# H4_PadController_Rev_1.net
KiCad netlist of a schematic drawn in EAGLE
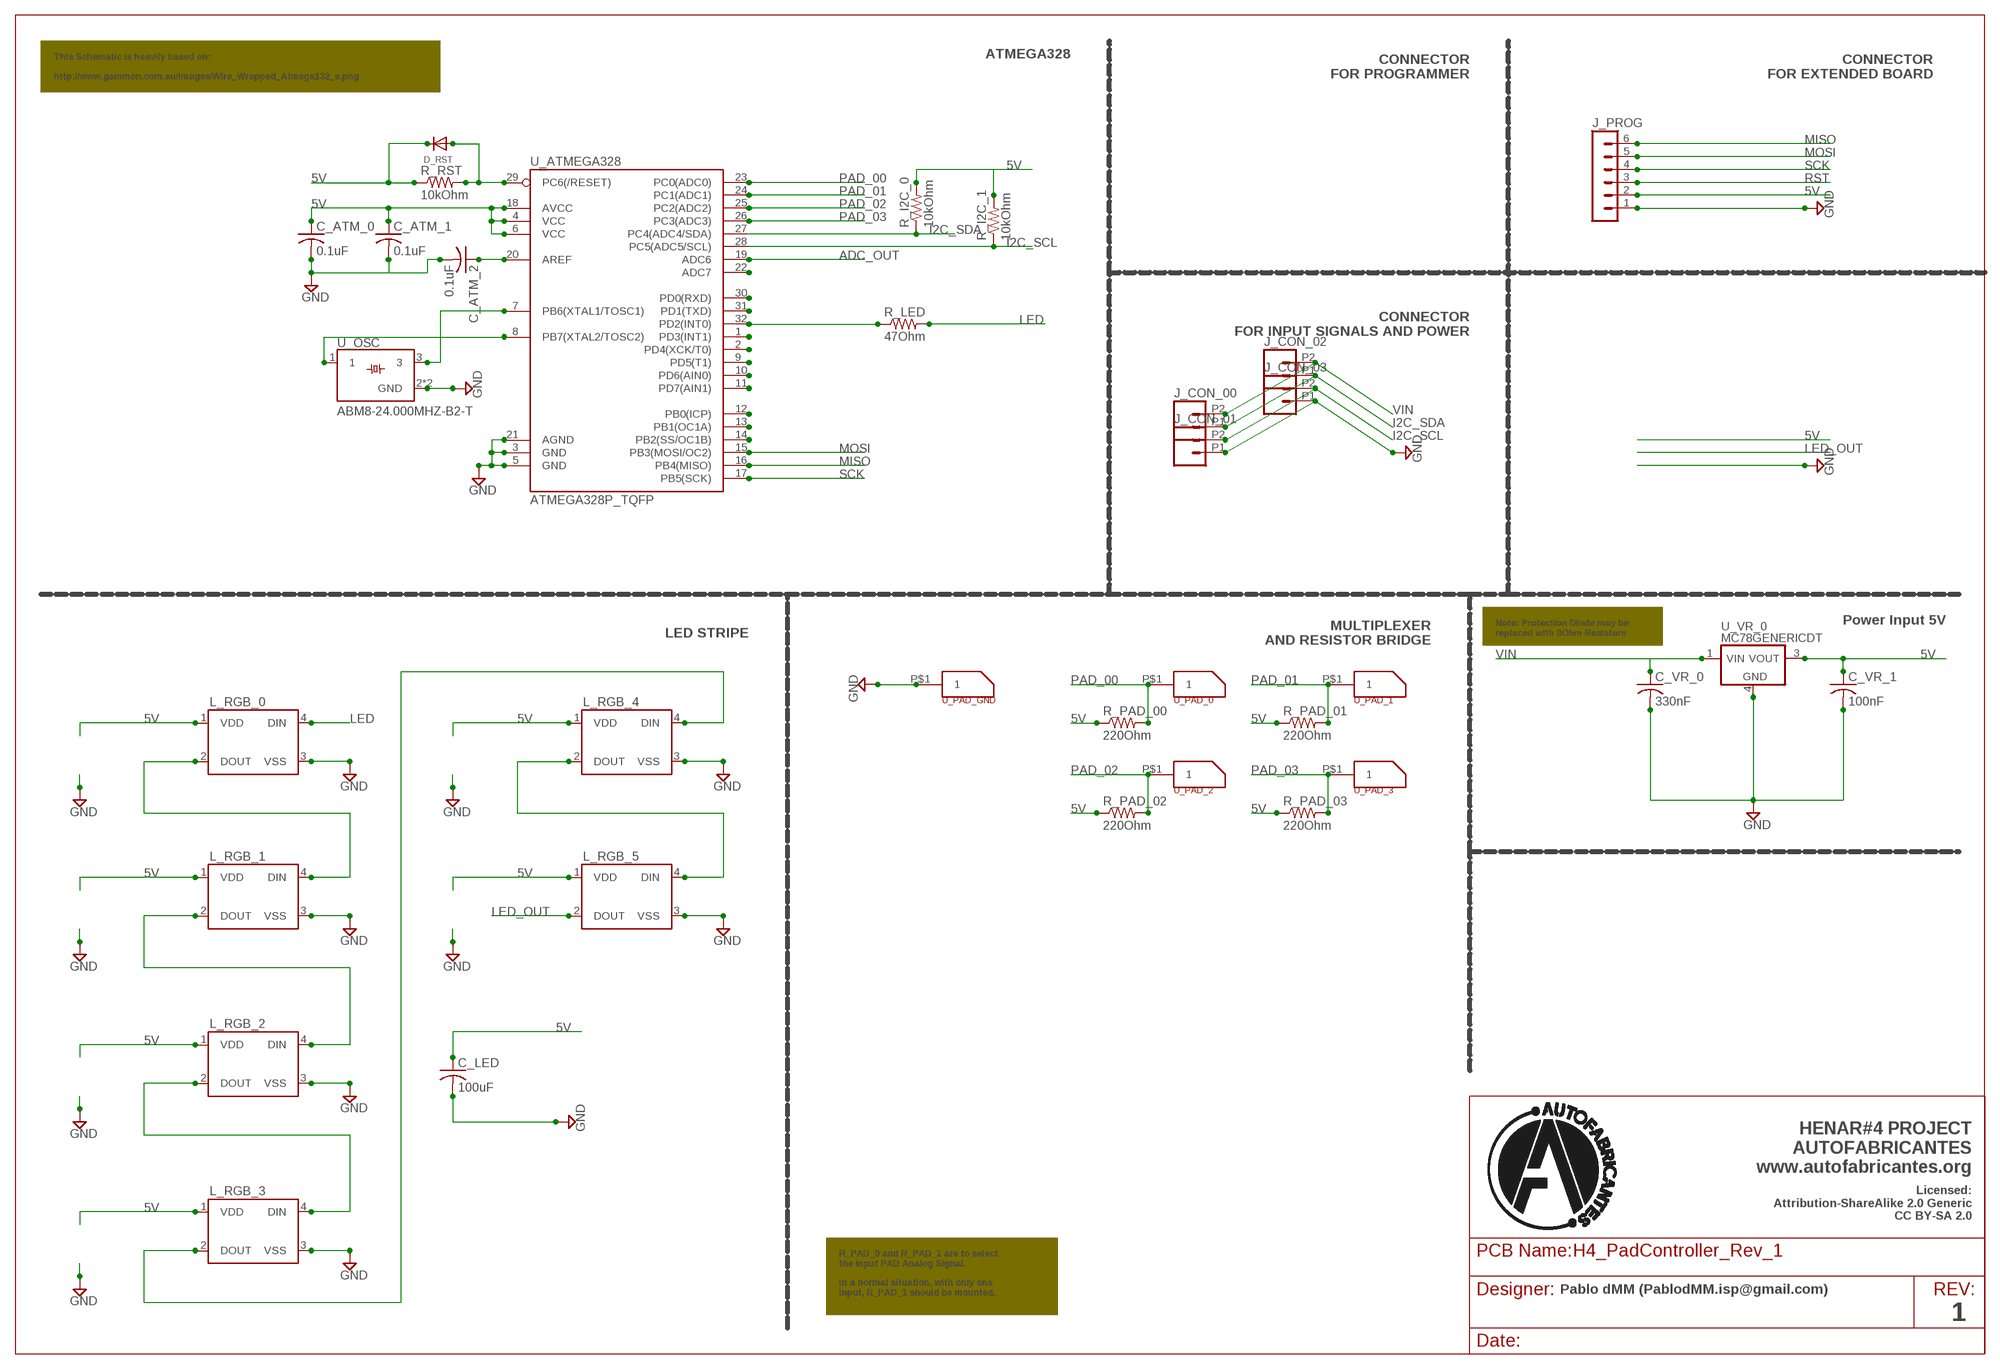
[diagram p0: schematic, sheet 1]

(export (version "E")
  (design (tool "Eeschema 10.0.6"))
  (components
    (comp (ref "C_ATM_0")
      (value "0.1uF")
      (footprint "eagle-import:C0805")
      (libsource (lib "eagle-import") (part "C-USC0805"))
    )
    (comp (ref "C_ATM_1")
      (value "0.1uF")
      (footprint "eagle-import:C0805")
      (libsource (lib "eagle-import") (part "C-USC0805"))
    )
    (comp (ref "C_ATM_2")
      (value "0.1uF")
      (footprint "eagle-import:C0805")
      (libsource (lib "eagle-import") (part "C-USC0805"))
    )
    (comp (ref "C_LED")
      (value "100uF")
      (footprint "eagle-import:C1210")
      (libsource (lib "eagle-import") (part "C-USC1210"))
    )
    (comp (ref "C_VR_0")
      (value "330nF")
      (footprint "eagle-import:C0805")
      (libsource (lib "eagle-import") (part "C-USC0805"))
    )
    (comp (ref "C_VR_1")
      (value "100nF")
      (footprint "eagle-import:C0805")
      (libsource (lib "eagle-import") (part "C-USC0805"))
    )
    (comp (ref "D_RST")
      (value "DIODESOD-123")
      (footprint "eagle-import:SOD-123")
      (libsource (lib "eagle-import") (part "DIODESOD-123"))
    )
    (comp (ref "J_CON_00")
      (value "M022.54MM_SCREWTERM")
      (footprint "eagle-import:1X02_2.54_SCREWTERM")
      (libsource (lib "eagle-import") (part "M022.54MM_SCREWTERM"))
    )
    (comp (ref "J_CON_01")
      (value "M022.54MM_SCREWTERM")
      (footprint "eagle-import:1X02_2.54_SCREWTERM")
      (libsource (lib "eagle-import") (part "M022.54MM_SCREWTERM"))
    )
    (comp (ref "J_CON_02")
      (value "M022.54MM_SCREWTERM")
      (footprint "eagle-import:1X02_2.54_SCREWTERM")
      (libsource (lib "eagle-import") (part "M022.54MM_SCREWTERM"))
    )
    (comp (ref "J_CON_03")
      (value "M022.54MM_SCREWTERM")
      (footprint "eagle-import:1X02_2.54_SCREWTERM")
      (libsource (lib "eagle-import") (part "M022.54MM_SCREWTERM"))
    )
    (comp (ref "J_PROG")
      (value "MA06-1")
      (footprint "eagle-import:MA06-1")
      (libsource (lib "eagle-import") (part "MA06-1"))
    )
    (comp (ref "L_RGB_0")
      (value "WS2812B")
      (footprint "eagle-import:WS2812B")
      (libsource (lib "eagle-import") (part "WS2812B"))
    )
    (comp (ref "L_RGB_1")
      (value "WS2812B")
      (footprint "eagle-import:WS2812B")
      (libsource (lib "eagle-import") (part "WS2812B"))
    )
    (comp (ref "L_RGB_2")
      (value "WS2812B")
      (footprint "eagle-import:WS2812B")
      (libsource (lib "eagle-import") (part "WS2812B"))
    )
    (comp (ref "L_RGB_3")
      (value "WS2812B")
      (footprint "eagle-import:WS2812B")
      (libsource (lib "eagle-import") (part "WS2812B"))
    )
    (comp (ref "L_RGB_4")
      (value "WS2812B")
      (footprint "eagle-import:WS2812B")
      (libsource (lib "eagle-import") (part "WS2812B"))
    )
    (comp (ref "L_RGB_5")
      (value "WS2812B")
      (footprint "eagle-import:WS2812B")
      (libsource (lib "eagle-import") (part "WS2812B"))
    )
    (comp (ref "R_I2C_0")
      (value "10kOhm")
      (footprint "eagle-import:M0805")
      (libsource (lib "eagle-import") (part "R-US_M0805"))
    )
    (comp (ref "R_I2C_1")
      (value "10kOhm")
      (footprint "eagle-import:M0805")
      (libsource (lib "eagle-import") (part "R-US_M0805"))
    )
    (comp (ref "R_LED")
      (value "47Ohm")
      (footprint "eagle-import:M0805")
      (libsource (lib "eagle-import") (part "R-US_M0805"))
    )
    (comp (ref "R_PAD_00")
      (value "220Ohm")
      (footprint "eagle-import:M0805")
      (libsource (lib "eagle-import") (part "R-US_M0805"))
    )
    (comp (ref "R_PAD_01")
      (value "220Ohm")
      (footprint "eagle-import:M0805")
      (libsource (lib "eagle-import") (part "R-US_M0805"))
    )
    (comp (ref "R_PAD_02")
      (value "220Ohm")
      (footprint "eagle-import:M0805")
      (libsource (lib "eagle-import") (part "R-US_M0805"))
    )
    (comp (ref "R_PAD_03")
      (value "220Ohm")
      (footprint "eagle-import:M0805")
      (libsource (lib "eagle-import") (part "R-US_M0805"))
    )
    (comp (ref "R_RST")
      (value "10kOhm")
      (footprint "eagle-import:M0805")
      (libsource (lib "eagle-import") (part "R-US_M0805"))
    )
    (comp (ref "U_ATMEGA328")
      (value "ATMEGA328P_TQFP")
      (footprint "eagle-import:TQFP32-08")
      (libsource (lib "eagle-import") (part "ATMEGA328P_TQFP"))
    )
    (comp (ref "U_OSC")
      (value "ABM8-24.000MHZ-B2-T")
      (footprint "eagle-import:OSCSC320X250X100N")
      (fields (field (name "MF") "Abracon"))
      (libsource (lib "eagle-import") (part "ABM8-24.000MHZ-B2-T"))
    )
    (comp (ref "U_PAD_0")
      (value "PAD_CONNECTOR_MULTI")
      (footprint "eagle-import:PAD_CONNECTOR_MULTI")
      (libsource (lib "eagle-import") (part "PAD_CONNECTOR_MULTI"))
    )
    (comp (ref "U_PAD_1")
      (value "PAD_CONNECTOR_MULTI")
      (footprint "eagle-import:PAD_CONNECTOR_MULTI")
      (libsource (lib "eagle-import") (part "PAD_CONNECTOR_MULTI"))
    )
    (comp (ref "U_PAD_2")
      (value "PAD_CONNECTOR_MULTI")
      (footprint "eagle-import:PAD_CONNECTOR_MULTI")
      (libsource (lib "eagle-import") (part "PAD_CONNECTOR_MULTI"))
    )
    (comp (ref "U_PAD_3")
      (value "PAD_CONNECTOR_MULTI")
      (footprint "eagle-import:PAD_CONNECTOR_MULTI")
      (libsource (lib "eagle-import") (part "PAD_CONNECTOR_MULTI"))
    )
    (comp (ref "U_PAD_GND")
      (value "PAD_CONNECTOR_MULTI")
      (footprint "eagle-import:PAD_CONNECTOR_MULTI")
      (libsource (lib "eagle-import") (part "PAD_CONNECTOR_MULTI"))
    )
    (comp (ref "U_VR_0")
      (value "MC78GENERICDT")
      (footprint "eagle-import:DPAK-3")
      (libsource (lib "eagle-import") (part "MC78DTGENERIC"))
    )
  )
  (nets
    (net (code "1") (name "/5V") (class "Default")
      (node (ref "C_ATM_0") (pin "1") (pinfunction "1_1") (pintype "passive"))
      (node (ref "C_ATM_1") (pin "1") (pinfunction "1_1") (pintype "passive"))
      (node (ref "C_LED") (pin "1") (pinfunction "1_1") (pintype "passive"))
      (node (ref "C_VR_1") (pin "1") (pinfunction "1_1") (pintype "passive"))
      (node (ref "D_RST") (pin "C") (pinfunction "C_C") (pintype "passive"))
      (node (ref "J_PROG") (pin "2") (pinfunction "2_2") (pintype "passive"))
      (node (ref "L_RGB_0") (pin "1") (pinfunction "VDD_1") (pintype "power_in"))
      (node (ref "L_RGB_1") (pin "1") (pinfunction "VDD_1") (pintype "power_in"))
      (node (ref "L_RGB_2") (pin "1") (pinfunction "VDD_1") (pintype "power_in"))
      (node (ref "L_RGB_3") (pin "1") (pinfunction "VDD_1") (pintype "power_in"))
      (node (ref "L_RGB_4") (pin "1") (pinfunction "VDD_1") (pintype "power_in"))
      (node (ref "L_RGB_5") (pin "1") (pinfunction "VDD_1") (pintype "power_in"))
      (node (ref "R_I2C_0") (pin "2") (pinfunction "2_2") (pintype "passive"))
      (node (ref "R_I2C_1") (pin "2") (pinfunction "2_2") (pintype "passive"))
      (node (ref "R_PAD_00") (pin "1") (pinfunction "1_1") (pintype "passive"))
      (node (ref "R_PAD_01") (pin "1") (pinfunction "1_1") (pintype "passive"))
      (node (ref "R_PAD_02") (pin "1") (pinfunction "1_1") (pintype "passive"))
      (node (ref "R_PAD_03") (pin "1") (pinfunction "1_1") (pintype "passive"))
      (node (ref "R_RST") (pin "1") (pinfunction "1_1") (pintype "passive"))
      (node (ref "U_ATMEGA328") (pin "18") (pinfunction "AVCC_18") (pintype "bidirectional"))
      (node (ref "U_ATMEGA328") (pin "4") (pinfunction "VCC_4") (pintype "bidirectional"))
      (node (ref "U_ATMEGA328") (pin "6") (pinfunction "VCC_6") (pintype "bidirectional"))
      (node (ref "U_VR_0") (pin "3") (pinfunction "VOUT_3") (pintype "power_in"))
    )
    (net (code "2") (name "/ADC_OUT") (class "Default")
      (node (ref "U_ATMEGA328") (pin "19") (pinfunction "ADC6_19") (pintype "bidirectional"))
    )
    (net (code "3") (name "/I2C_SCL") (class "Default")
      (node (ref "J_CON_01") (pin "P2") (pinfunction "2_P2") (pintype "passive"))
      (node (ref "J_CON_03") (pin "P2") (pinfunction "2_P2") (pintype "passive"))
      (node (ref "R_I2C_1") (pin "1") (pinfunction "1_1") (pintype "passive"))
      (node (ref "U_ATMEGA328") (pin "28") (pinfunction "PC5(ADC5/SCL)_28") (pintype "bidirectional"))
    )
    (net (code "4") (name "/I2C_SDA") (class "Default")
      (node (ref "J_CON_00") (pin "P1") (pinfunction "1_P1") (pintype "passive"))
      (node (ref "J_CON_02") (pin "P1") (pinfunction "1_P1") (pintype "passive"))
      (node (ref "R_I2C_0") (pin "1") (pinfunction "1_1") (pintype "passive"))
      (node (ref "U_ATMEGA328") (pin "27") (pinfunction "PC4(ADC4/SDA)_27") (pintype "bidirectional"))
    )
    (net (code "5") (name "/LED") (class "Default")
      (node (ref "L_RGB_0") (pin "4") (pinfunction "DIN_4") (pintype "input"))
      (node (ref "R_LED") (pin "2") (pinfunction "2_2") (pintype "passive"))
    )
    (net (code "6") (name "/LED_OUT") (class "Default")
      (node (ref "L_RGB_5") (pin "2") (pinfunction "DOUT_2") (pintype "output"))
    )
    (net (code "7") (name "/MISO") (class "Default")
      (node (ref "J_PROG") (pin "6") (pinfunction "6_6") (pintype "passive"))
      (node (ref "U_ATMEGA328") (pin "16") (pinfunction "PB4(MISO)_16") (pintype "bidirectional"))
    )
    (net (code "8") (name "/MOSI") (class "Default")
      (node (ref "J_PROG") (pin "5") (pinfunction "5_5") (pintype "passive"))
      (node (ref "U_ATMEGA328") (pin "15") (pinfunction "PB3(MOSI/OC2)_15") (pintype "bidirectional"))
    )
    (net (code "9") (name "/PAD_00") (class "Default")
      (node (ref "R_PAD_00") (pin "2") (pinfunction "2_2") (pintype "passive"))
      (node (ref "U_ATMEGA328") (pin "23") (pinfunction "PC0(ADC0)_23") (pintype "bidirectional"))
      (node (ref "U_PAD_0") (pin "P$1") (pinfunction "1_P$1") (pintype "bidirectional"))
    )
    (net (code "10") (name "/PAD_01") (class "Default")
      (node (ref "R_PAD_01") (pin "2") (pinfunction "2_2") (pintype "passive"))
      (node (ref "U_ATMEGA328") (pin "24") (pinfunction "PC1(ADC1)_24") (pintype "bidirectional"))
      (node (ref "U_PAD_1") (pin "P$1") (pinfunction "1_P$1") (pintype "bidirectional"))
    )
    (net (code "11") (name "/PAD_02") (class "Default")
      (node (ref "R_PAD_02") (pin "2") (pinfunction "2_2") (pintype "passive"))
      (node (ref "U_ATMEGA328") (pin "25") (pinfunction "PC2(ADC2)_25") (pintype "bidirectional"))
      (node (ref "U_PAD_2") (pin "P$1") (pinfunction "1_P$1") (pintype "bidirectional"))
    )
    (net (code "12") (name "/PAD_03") (class "Default")
      (node (ref "R_PAD_03") (pin "2") (pinfunction "2_2") (pintype "passive"))
      (node (ref "U_ATMEGA328") (pin "26") (pinfunction "PC3(ADC3)_26") (pintype "bidirectional"))
      (node (ref "U_PAD_3") (pin "P$1") (pinfunction "1_P$1") (pintype "bidirectional"))
    )
    (net (code "13") (name "/RST") (class "Default")
      (node (ref "D_RST") (pin "A") (pinfunction "A_A") (pintype "passive"))
      (node (ref "J_PROG") (pin "3") (pinfunction "3_3") (pintype "passive"))
      (node (ref "R_RST") (pin "2") (pinfunction "2_2") (pintype "passive"))
      (node (ref "U_ATMEGA328") (pin "29") (pinfunction "PC6(/RESET)_29") (pintype "bidirectional"))
    )
    (net (code "14") (name "/SCK") (class "Default")
      (node (ref "J_PROG") (pin "4") (pinfunction "4_4") (pintype "passive"))
      (node (ref "U_ATMEGA328") (pin "17") (pinfunction "PB5(SCK)_17") (pintype "bidirectional"))
    )
    (net (code "15") (name "/VIN") (class "Default")
      (node (ref "C_VR_0") (pin "1") (pinfunction "1_1") (pintype "passive"))
      (node (ref "J_CON_00") (pin "P2") (pinfunction "2_P2") (pintype "passive"))
      (node (ref "J_CON_02") (pin "P2") (pinfunction "2_P2") (pintype "passive"))
      (node (ref "U_VR_0") (pin "1") (pinfunction "VIN_1") (pintype "power_in"))
    )
    (net (code "16") (name "GND") (class "Default")
      (node (ref "C_ATM_0") (pin "2") (pinfunction "2_2") (pintype "passive"))
      (node (ref "C_ATM_1") (pin "2") (pinfunction "2_2") (pintype "passive"))
      (node (ref "C_ATM_2") (pin "2") (pinfunction "2_2") (pintype "passive"))
      (node (ref "C_LED") (pin "2") (pinfunction "2_2") (pintype "passive"))
      (node (ref "C_VR_0") (pin "2") (pinfunction "2_2") (pintype "passive"))
      (node (ref "C_VR_1") (pin "2") (pinfunction "2_2") (pintype "passive"))
      (node (ref "J_CON_01") (pin "P1") (pinfunction "1_P1") (pintype "passive"))
      (node (ref "J_CON_03") (pin "P1") (pinfunction "1_P1") (pintype "passive"))
      (node (ref "J_PROG") (pin "1") (pinfunction "1_1") (pintype "passive"))
      (node (ref "L_RGB_0") (pin "3") (pinfunction "VSS_3") (pintype "power_in"))
      (node (ref "L_RGB_1") (pin "3") (pinfunction "VSS_3") (pintype "power_in"))
      (node (ref "L_RGB_2") (pin "3") (pinfunction "VSS_3") (pintype "power_in"))
      (node (ref "L_RGB_3") (pin "3") (pinfunction "VSS_3") (pintype "power_in"))
      (node (ref "L_RGB_4") (pin "3") (pinfunction "VSS_3") (pintype "power_in"))
      (node (ref "L_RGB_5") (pin "3") (pinfunction "VSS_3") (pintype "power_in"))
      (node (ref "U_ATMEGA328") (pin "21") (pinfunction "AGND_21") (pintype "bidirectional"))
      (node (ref "U_ATMEGA328") (pin "3") (pinfunction "GND_3") (pintype "bidirectional"))
      (node (ref "U_ATMEGA328") (pin "5") (pinfunction "GND_5") (pintype "bidirectional"))
      (node (ref "U_OSC") (pin "2") (pinfunction "GND_2") (pintype "power_in"))
      (node (ref "U_OSC") (pin "4") (pinfunction "GND_4") (pintype "power_in"))
      (node (ref "U_PAD_GND") (pin "P$1") (pinfunction "1_P$1") (pintype "bidirectional"))
      (node (ref "U_VR_0") (pin "4") (pinfunction "GND_4") (pintype "power_in"))
    )
    (net (code "17") (name "Net-(L_RGB_0-DOUT)") (class "Default")
      (node (ref "L_RGB_0") (pin "2") (pinfunction "DOUT_2") (pintype "output"))
      (node (ref "L_RGB_1") (pin "4") (pinfunction "DIN_4") (pintype "input"))
    )
    (net (code "18") (name "Net-(L_RGB_1-DOUT)") (class "Default")
      (node (ref "L_RGB_1") (pin "2") (pinfunction "DOUT_2") (pintype "output"))
      (node (ref "L_RGB_2") (pin "4") (pinfunction "DIN_4") (pintype "input"))
    )
    (net (code "19") (name "Net-(L_RGB_2-DOUT)") (class "Default")
      (node (ref "L_RGB_2") (pin "2") (pinfunction "DOUT_2") (pintype "output"))
      (node (ref "L_RGB_3") (pin "4") (pinfunction "DIN_4") (pintype "input"))
    )
    (net (code "20") (name "Net-(L_RGB_3-DOUT)") (class "Default")
      (node (ref "L_RGB_3") (pin "2") (pinfunction "DOUT_2") (pintype "output"))
      (node (ref "L_RGB_4") (pin "4") (pinfunction "DIN_4") (pintype "input"))
    )
    (net (code "21") (name "Net-(L_RGB_4-DOUT)") (class "Default")
      (node (ref "L_RGB_4") (pin "2") (pinfunction "DOUT_2") (pintype "output"))
      (node (ref "L_RGB_5") (pin "4") (pinfunction "DIN_4") (pintype "input"))
    )
    (net (code "22") (name "Net-(U_ATMEGA328-AREF)") (class "Default")
      (node (ref "C_ATM_2") (pin "1") (pinfunction "1_1") (pintype "passive"))
      (node (ref "U_ATMEGA328") (pin "20") (pinfunction "AREF_20") (pintype "bidirectional"))
    )
    (net (code "23") (name "Net-(U_ATMEGA328-PB6(XTAL1{slash}TOSC1))") (class "Default")
      (node (ref "U_ATMEGA328") (pin "7") (pinfunction "PB6(XTAL1/TOSC1)_7") (pintype "bidirectional"))
      (node (ref "U_OSC") (pin "3") (pinfunction "3_3") (pintype "passive"))
    )
    (net (code "24") (name "Net-(U_ATMEGA328-PB7(XTAL2{slash}TOSC2))") (class "Default")
      (node (ref "U_ATMEGA328") (pin "8") (pinfunction "PB7(XTAL2/TOSC2)_8") (pintype "bidirectional"))
      (node (ref "U_OSC") (pin "1") (pinfunction "1_1") (pintype "passive"))
    )
    (net (code "25") (name "Net-(U_ATMEGA328-PD2(INT0))") (class "Default")
      (node (ref "R_LED") (pin "1") (pinfunction "1_1") (pintype "passive"))
      (node (ref "U_ATMEGA328") (pin "32") (pinfunction "PD2(INT0)_32") (pintype "bidirectional"))
    )
    (net (code "26") (name "unconnected-(U_ATMEGA328-ADC7-Pad22)") (class "Default")
      (node (ref "U_ATMEGA328") (pin "22") (pinfunction "ADC7_22") (pintype "bidirectional"))
    )
    (net (code "27") (name "unconnected-(U_ATMEGA328-PB0(ICP)-Pad12)") (class "Default")
      (node (ref "U_ATMEGA328") (pin "12") (pinfunction "PB0(ICP)_12") (pintype "bidirectional"))
    )
    (net (code "28") (name "unconnected-(U_ATMEGA328-PB1(OC1A)-Pad13)") (class "Default")
      (node (ref "U_ATMEGA328") (pin "13") (pinfunction "PB1(OC1A)_13") (pintype "bidirectional"))
    )
    (net (code "29") (name "unconnected-(U_ATMEGA328-PB2(SS{slash}OC1B)-Pad14)") (class "Default")
      (node (ref "U_ATMEGA328") (pin "14") (pinfunction "PB2(SS/OC1B)_14") (pintype "bidirectional"))
    )
    (net (code "30") (name "unconnected-(U_ATMEGA328-PD0(RXD)-Pad30)") (class "Default")
      (node (ref "U_ATMEGA328") (pin "30") (pinfunction "PD0(RXD)_30") (pintype "bidirectional"))
    )
    (net (code "31") (name "unconnected-(U_ATMEGA328-PD1(TXD)-Pad31)") (class "Default")
      (node (ref "U_ATMEGA328") (pin "31") (pinfunction "PD1(TXD)_31") (pintype "bidirectional"))
    )
    (net (code "32") (name "unconnected-(U_ATMEGA328-PD3(INT1)-Pad1)") (class "Default")
      (node (ref "U_ATMEGA328") (pin "1") (pinfunction "PD3(INT1)_1") (pintype "bidirectional"))
    )
    (net (code "33") (name "unconnected-(U_ATMEGA328-PD4(XCK{slash}T0)-Pad2)") (class "Default")
      (node (ref "U_ATMEGA328") (pin "2") (pinfunction "PD4(XCK/T0)_2") (pintype "bidirectional"))
    )
    (net (code "34") (name "unconnected-(U_ATMEGA328-PD5(T1)-Pad9)") (class "Default")
      (node (ref "U_ATMEGA328") (pin "9") (pinfunction "PD5(T1)_9") (pintype "bidirectional"))
    )
    (net (code "35") (name "unconnected-(U_ATMEGA328-PD6(AIN0)-Pad10)") (class "Default")
      (node (ref "U_ATMEGA328") (pin "10") (pinfunction "PD6(AIN0)_10") (pintype "bidirectional"))
    )
    (net (code "36") (name "unconnected-(U_ATMEGA328-PD7(AIN1)-Pad11)") (class "Default")
      (node (ref "U_ATMEGA328") (pin "11") (pinfunction "PD7(AIN1)_11") (pintype "bidirectional"))
    )
  )
)
